# BitDogLab_V7.net
KiCad netlist of a schematic drawn in Altium Designer
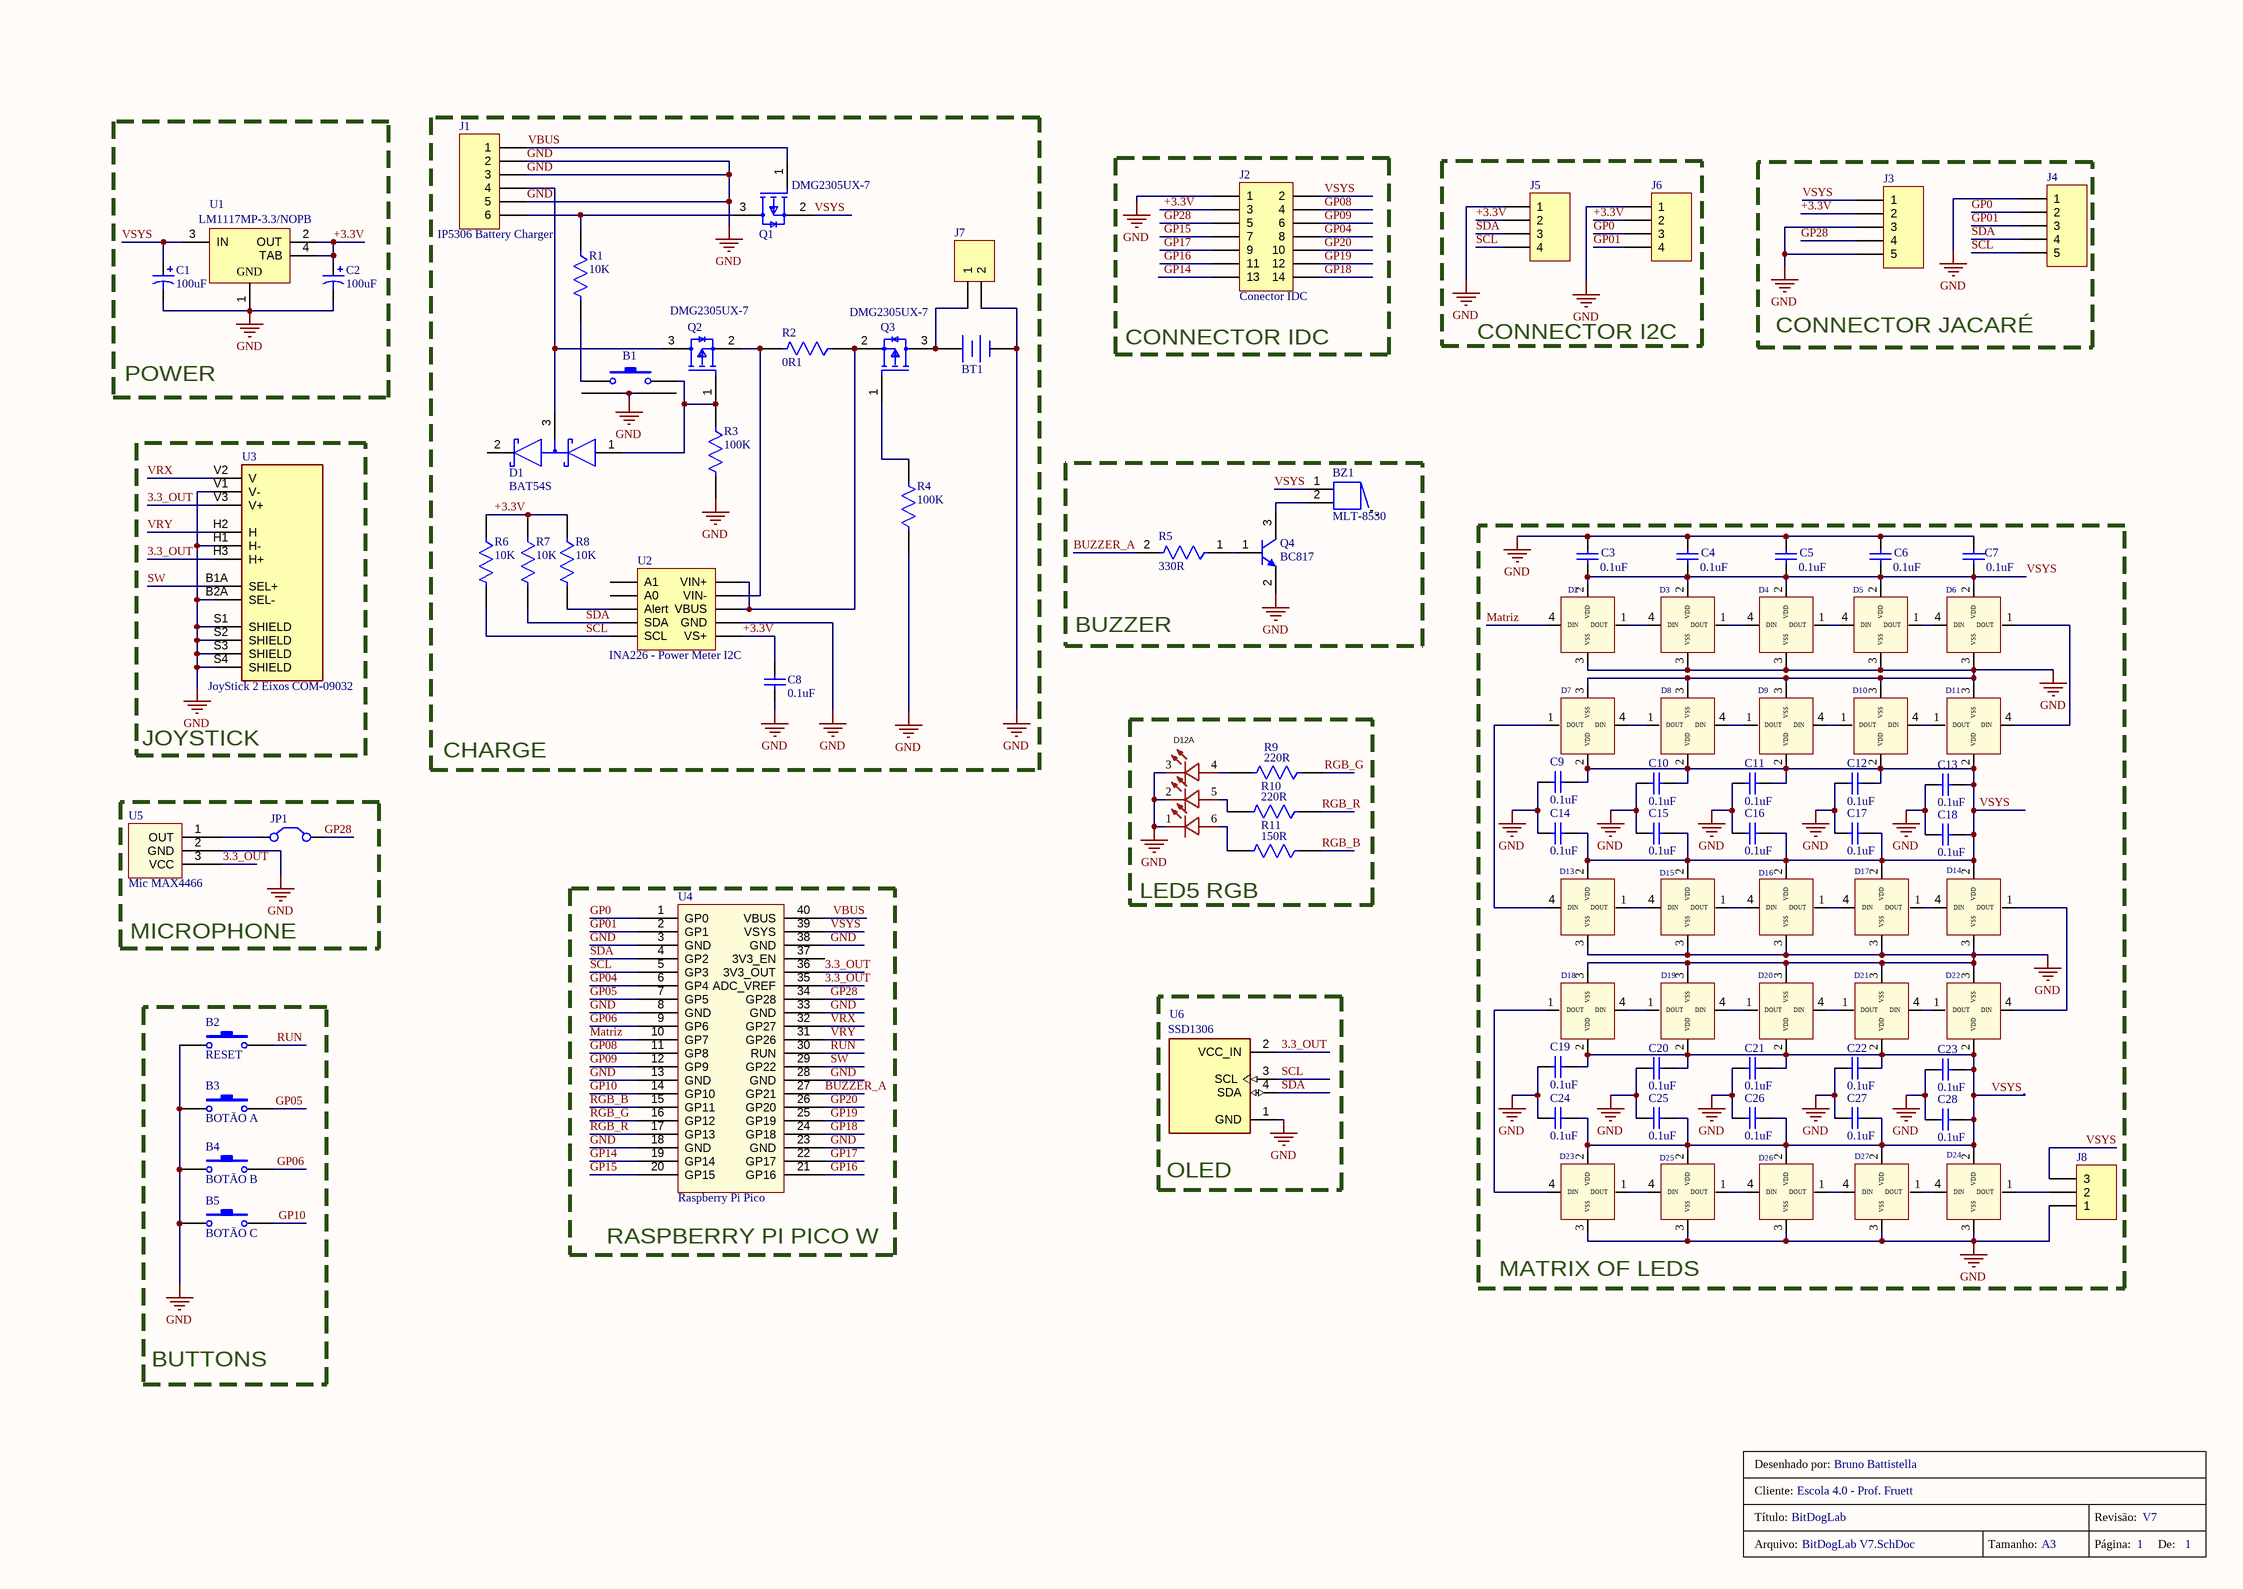
[diagram p0: BitDogLab V7.SchDoc]

(export (version "E")
  (design (tool "Eeschema 10.0.6"))
  (components
    (comp (ref "B1")
      (value "Desliga")
      (footprint "Componentes e Conectores:CHAVE TÁCTIL SMD 90")
      (description "Botão Desliga Placa")
      (libsource (lib "Componentes Bruno") (part "Push Buttom SMD 90 graus"))
    )
    (comp (ref "B2")
      (value "RESET")
      (footprint "Componentes e Conectores:CHAVE TÁCTIL SMD")
      (description "Botão Reset")
      (libsource (lib "Miscellaneous Devices") (part "SW-PB"))
    )
    (comp (ref "B3")
      (value "BOTÃO A")
      (footprint "Componentes e Conectores:CHAVE TÁCTIL 12mm - SMD")
      (description "CHAVE TÁCTIL 12mm - SMD")
      (libsource (lib "Miscellaneous Devices") (part "SW-PB"))
    )
    (comp (ref "B4")
      (value "BOTÃO B")
      (footprint "Componentes e Conectores:CHAVE TÁCTIL 12mm - SMD")
      (description "CHAVE TÁCTIL 12mm - SMD")
      (libsource (lib "Miscellaneous Devices") (part "SW-PB"))
    )
    (comp (ref "B5")
      (value "BOTÃO C")
      (footprint "Componentes e Conectores:CHAVE TÁCTIL 12mm - SMD")
      (description "CHAVE TÁCTIL 12mm - SMD")
      (libsource (lib "Miscellaneous Devices") (part "SW-PB"))
    )
    (comp (ref "BT1")
      (value "FP-1043P-MFG")
      (footprint "Componentes e Conectores:Bateria 18650 - SMD")
      (description "Bateria 18650 3,7V")
      (libsource (lib "Miscellaneous Devices") (part "Battery"))
    )
    (comp (ref "BZ1")
      (value "MLT-8530")
      (footprint "Componentes e Conectores:Buzzer SMD - MLT-8530")
      (description "Buzzer SMD")
      (libsource (lib "Miscellaneous Devices") (part "Buzzer"))
    )
    (comp (ref "C1")
      (value "100uF")
      (footprint "Componentes e Conectores:Capacitor SMD - 6.3 x 5.4mm")
      (description "Capacitor Eletrolítico 100uF  SMD 6.3 x 5.4 mm")
      (fields (field (name "Comment") "Capacitor Eletrolítico SMD,D6.3xL5.4mm"))
      (libsource (lib "Miscellaneous Devices") (part "Cap Pol1"))
    )
    (comp (ref "C2")
      (value "100uF")
      (footprint "Componentes e Conectores:Capacitor SMD - 6.3 x 5.4mm")
      (description "Capacitor Eletrolítico 100uF  SMD 6.3 x 5.4 mm")
      (fields (field (name "Comment") "Capacitor Eletrolítico SMD,D6.3xL5.4mm"))
      (libsource (lib "Miscellaneous Devices") (part "Cap Pol1"))
    )
    (comp (ref "C3")
      (value "0.1uF")
      (footprint "Componentes e Conectores:Capacitor SMD 0402")
      (description "Capacitor SMD 0402")
      (fields (field (name "Comment") "Cap"))
      (libsource (lib "Miscellaneous Devices") (part "Cap"))
    )
    (comp (ref "C4")
      (value "0.1uF")
      (footprint "Componentes e Conectores:Capacitor SMD 0402")
      (description "Capacitor SMD 0402")
      (fields (field (name "Comment") "Cap"))
      (libsource (lib "Miscellaneous Devices") (part "Cap"))
    )
    (comp (ref "C5")
      (value "0.1uF")
      (footprint "Componentes e Conectores:Capacitor SMD 0402")
      (description "Capacitor SMD 0402")
      (fields (field (name "Comment") "Cap"))
      (libsource (lib "Miscellaneous Devices") (part "Cap"))
    )
    (comp (ref "C6")
      (value "0.1uF")
      (footprint "Componentes e Conectores:Capacitor SMD 0402")
      (description "Capacitor SMD 0402")
      (fields (field (name "Comment") "Cap"))
      (libsource (lib "Miscellaneous Devices") (part "Cap"))
    )
    (comp (ref "C7")
      (value "0.1uF")
      (footprint "Componentes e Conectores:Capacitor SMD 0402")
      (description "Capacitor SMD 0402")
      (fields (field (name "Comment") "Cap"))
      (libsource (lib "Miscellaneous Devices") (part "Cap"))
    )
    (comp (ref "C8")
      (value "0.1uF")
      (footprint "Componentes e Conectores:Capacitor SMD 0603")
      (description "Capacitor SMD 0402")
      (fields (field (name "Comment") "Cap"))
      (libsource (lib "Miscellaneous Devices") (part "Cap"))
    )
    (comp (ref "C9")
      (value "0.1uF")
      (footprint "Componentes e Conectores:Capacitor SMD 0402")
      (description "Capacitor SMD 0402")
      (fields (field (name "Comment") "Cap"))
      (libsource (lib "Miscellaneous Devices") (part "Cap"))
    )
    (comp (ref "C10")
      (value "0.1uF")
      (footprint "Componentes e Conectores:Capacitor SMD 0402")
      (description "Capacitor SMD 0402")
      (fields (field (name "Comment") "Cap"))
      (libsource (lib "Miscellaneous Devices") (part "Cap"))
    )
    (comp (ref "C11")
      (value "0.1uF")
      (footprint "Componentes e Conectores:Capacitor SMD 0402")
      (description "Capacitor SMD 0402")
      (fields (field (name "Comment") "Cap"))
      (libsource (lib "Miscellaneous Devices") (part "Cap"))
    )
    (comp (ref "C12")
      (value "0.1uF")
      (footprint "Componentes e Conectores:Capacitor SMD 0402")
      (description "Capacitor SMD 0402")
      (fields (field (name "Comment") "Cap"))
      (libsource (lib "Miscellaneous Devices") (part "Cap"))
    )
    (comp (ref "C13")
      (value "0.1uF")
      (footprint "Componentes e Conectores:Capacitor SMD 0402")
      (description "Capacitor SMD 0402")
      (fields (field (name "Comment") "Cap"))
      (libsource (lib "Miscellaneous Devices") (part "Cap"))
    )
    (comp (ref "C14")
      (value "0.1uF")
      (footprint "Componentes e Conectores:Capacitor SMD 0402")
      (description "Capacitor SMD 0402")
      (fields (field (name "Comment") "Cap"))
      (libsource (lib "Miscellaneous Devices") (part "Cap"))
    )
    (comp (ref "C15")
      (value "0.1uF")
      (footprint "Componentes e Conectores:Capacitor SMD 0402")
      (description "Capacitor SMD 0402")
      (fields (field (name "Comment") "Cap"))
      (libsource (lib "Miscellaneous Devices") (part "Cap"))
    )
    (comp (ref "C16")
      (value "0.1uF")
      (footprint "Componentes e Conectores:Capacitor SMD 0402")
      (description "Capacitor SMD 0402")
      (fields (field (name "Comment") "Cap"))
      (libsource (lib "Miscellaneous Devices") (part "Cap"))
    )
    (comp (ref "C17")
      (value "0.1uF")
      (footprint "Componentes e Conectores:Capacitor SMD 0402")
      (description "Capacitor SMD 0402")
      (fields (field (name "Comment") "Cap"))
      (libsource (lib "Miscellaneous Devices") (part "Cap"))
    )
    (comp (ref "C18")
      (value "0.1uF")
      (footprint "Componentes e Conectores:Capacitor SMD 0402")
      (description "Capacitor SMD 0402")
      (fields (field (name "Comment") "Cap"))
      (libsource (lib "Miscellaneous Devices") (part "Cap"))
    )
    (comp (ref "C19")
      (value "0.1uF")
      (footprint "Componentes e Conectores:Capacitor SMD 0402")
      (description "Capacitor SMD 0402")
      (fields (field (name "Comment") "Cap"))
      (libsource (lib "Miscellaneous Devices") (part "Cap"))
    )
    (comp (ref "C20")
      (value "0.1uF")
      (footprint "Componentes e Conectores:Capacitor SMD 0402")
      (description "Capacitor SMD 0402")
      (fields (field (name "Comment") "Cap"))
      (libsource (lib "Miscellaneous Devices") (part "Cap"))
    )
    (comp (ref "C21")
      (value "0.1uF")
      (footprint "Componentes e Conectores:Capacitor SMD 0402")
      (description "Capacitor SMD 0402")
      (fields (field (name "Comment") "Cap"))
      (libsource (lib "Miscellaneous Devices") (part "Cap"))
    )
    (comp (ref "C22")
      (value "0.1uF")
      (footprint "Componentes e Conectores:Capacitor SMD 0402")
      (description "Capacitor SMD 0402")
      (fields (field (name "Comment") "Cap"))
      (libsource (lib "Miscellaneous Devices") (part "Cap"))
    )
    (comp (ref "C23")
      (value "0.1uF")
      (footprint "Componentes e Conectores:Capacitor SMD 0402")
      (description "Capacitor SMD 0402")
      (fields (field (name "Comment") "Cap"))
      (libsource (lib "Miscellaneous Devices") (part "Cap"))
    )
    (comp (ref "C24")
      (value "0.1uF")
      (footprint "Componentes e Conectores:Capacitor SMD 0402")
      (description "Capacitor SMD 0402")
      (fields (field (name "Comment") "Cap"))
      (libsource (lib "Miscellaneous Devices") (part "Cap"))
    )
    (comp (ref "C25")
      (value "0.1uF")
      (footprint "Componentes e Conectores:Capacitor SMD 0402")
      (description "Capacitor SMD 0402")
      (fields (field (name "Comment") "Cap"))
      (libsource (lib "Miscellaneous Devices") (part "Cap"))
    )
    (comp (ref "C26")
      (value "0.1uF")
      (footprint "Componentes e Conectores:Capacitor SMD 0402")
      (description "Capacitor SMD 0402")
      (fields (field (name "Comment") "Cap"))
      (libsource (lib "Miscellaneous Devices") (part "Cap"))
    )
    (comp (ref "C27")
      (value "0.1uF")
      (footprint "Componentes e Conectores:Capacitor SMD 0402")
      (description "Capacitor SMD 0402")
      (fields (field (name "Comment") "Cap"))
      (libsource (lib "Miscellaneous Devices") (part "Cap"))
    )
    (comp (ref "C28")
      (value "0.1uF")
      (footprint "Componentes e Conectores:Capacitor SMD 0402")
      (description "Capacitor SMD 0402")
      (fields (field (name "Comment") "Cap"))
      (libsource (lib "Miscellaneous Devices") (part "Cap"))
    )
    (comp (ref "D1")
      (value "BAT54S")
      (footprint "FP-6_541-5014_01-4-MFG")
      (description "Diodo Schottky SOT23")
      (fields
        (field (name "MANUFACTURER PART NUMBER") "BAT54S-E3-08")
        (field (name "OCTOPART") "https://octopart.com/bat54s-e3-08-vishay-29186616")
      )
      (libsource (lib "Altium Content Vault") (part "826853e049917e74922d2434823b145"))
    )
    (comp (ref "D2")
      (value "XINGLIGHT XL-1615RGBC-WS2812B")
      (footprint "Componentes e Conectores:LED RGB - XL-1615RGBC-WS2812B")
      (description "LED RGB Endereçável")
      (libsource (lib "Componentes Bruno") (part "LED RGB XL-1615RGBC-WS2812B"))
    )
    (comp (ref "D3")
      (value "XINGLIGHT XL-1615RGBC-WS2812B")
      (footprint "Componentes e Conectores:LED RGB - XL-1615RGBC-WS2812B")
      (description "LED RGB Endereçável")
      (libsource (lib "Componentes Bruno") (part "LED RGB XL-1615RGBC-WS2812B"))
    )
    (comp (ref "D4")
      (value "XINGLIGHT XL-1615RGBC-WS2812B")
      (footprint "Componentes e Conectores:LED RGB - XL-1615RGBC-WS2812B")
      (description "LED RGB Endereçável")
      (libsource (lib "Componentes Bruno") (part "LED RGB XL-1615RGBC-WS2812B"))
    )
    (comp (ref "D5")
      (value "XINGLIGHT XL-1615RGBC-WS2812B")
      (footprint "Componentes e Conectores:LED RGB - XL-1615RGBC-WS2812B")
      (description "LED RGB Endereçável")
      (libsource (lib "Componentes Bruno") (part "LED RGB XL-1615RGBC-WS2812B"))
    )
    (comp (ref "D6")
      (value "XINGLIGHT XL-1615RGBC-WS2812B")
      (footprint "Componentes e Conectores:LED RGB - XL-1615RGBC-WS2812B")
      (description "LED RGB Endereçável")
      (libsource (lib "Componentes Bruno") (part "LED RGB XL-1615RGBC-WS2812B"))
    )
    (comp (ref "D7")
      (value "XINGLIGHT XL-1615RGBC-WS2812B")
      (footprint "Componentes e Conectores:LED RGB - XL-1615RGBC-WS2812B")
      (description "LED RGB Endereçável")
      (libsource (lib "") (part "LED RGB XL-1615RGBC-WS2812B_1"))
    )
    (comp (ref "D8")
      (value "XINGLIGHT XL-1615RGBC-WS2812B")
      (footprint "Componentes e Conectores:LED RGB - XL-1615RGBC-WS2812B")
      (description "LED RGB Endereçável")
      (libsource (lib "") (part "LED RGB XL-1615RGBC-WS2812B_1"))
    )
    (comp (ref "D9")
      (value "XINGLIGHT XL-1615RGBC-WS2812B")
      (footprint "Componentes e Conectores:LED RGB - XL-1615RGBC-WS2812B")
      (description "LED RGB Endereçável")
      (libsource (lib "") (part "LED RGB XL-1615RGBC-WS2812B_1"))
    )
    (comp (ref "D10")
      (value "XINGLIGHT XL-1615RGBC-WS2812B")
      (footprint "Componentes e Conectores:LED RGB - XL-1615RGBC-WS2812B")
      (description "LED RGB Endereçável")
      (libsource (lib "") (part "LED RGB XL-1615RGBC-WS2812B_1"))
    )
    (comp (ref "D11")
      (value "XINGLIGHT XL-1615RGBC-WS2812B")
      (footprint "Componentes e Conectores:LED RGB - XL-1615RGBC-WS2812B")
      (description "LED RGB Endereçável")
      (libsource (lib "") (part "LED RGB XL-1615RGBC-WS2812B_1"))
    )
    (comp (ref "D12")
      (value "HL-AF-5060H271BU46FU79GC-S1-THL")
      (footprint "Componentes e Conectores:LED RGB SMD 5050")
      (description "LED RGB 5050")
      (fields (field (name "MANUFACTURER") "HONGLITRONIC(鸿利光电)"))
      (libsource (lib "Componentes Bruno") (part "LED_RGB_5050 - HL-AF-5060H271BU46FU79GC-S1-THL"))
    )
    (comp (ref "D13")
      (value "XINGLIGHT XL-1615RGBC-WS2812B")
      (footprint "Componentes e Conectores:LED RGB - XL-1615RGBC-WS2812B")
      (description "LED RGB Endereçável")
      (libsource (lib "Componentes Bruno") (part "LED RGB XL-1615RGBC-WS2812B"))
    )
    (comp (ref "D14")
      (value "XINGLIGHT XL-1615RGBC-WS2812B")
      (footprint "Componentes e Conectores:LED RGB - XL-1615RGBC-WS2812B")
      (description "LED RGB Endereçável")
      (libsource (lib "Componentes Bruno") (part "LED RGB XL-1615RGBC-WS2812B"))
    )
    (comp (ref "D15")
      (value "XINGLIGHT XL-1615RGBC-WS2812B")
      (footprint "Componentes e Conectores:LED RGB - XL-1615RGBC-WS2812B")
      (description "LED RGB Endereçável")
      (libsource (lib "Componentes Bruno") (part "LED RGB XL-1615RGBC-WS2812B"))
    )
    (comp (ref "D16")
      (value "XINGLIGHT XL-1615RGBC-WS2812B")
      (footprint "Componentes e Conectores:LED RGB - XL-1615RGBC-WS2812B")
      (description "LED RGB Endereçável")
      (libsource (lib "Componentes Bruno") (part "LED RGB XL-1615RGBC-WS2812B"))
    )
    (comp (ref "D17")
      (value "XINGLIGHT XL-1615RGBC-WS2812B")
      (footprint "Componentes e Conectores:LED RGB - XL-1615RGBC-WS2812B")
      (description "LED RGB Endereçável")
      (libsource (lib "Componentes Bruno") (part "LED RGB XL-1615RGBC-WS2812B"))
    )
    (comp (ref "D18")
      (value "XINGLIGHT XL-1615RGBC-WS2812B")
      (footprint "Componentes e Conectores:LED RGB - XL-1615RGBC-WS2812B")
      (description "LED RGB Endereçável")
      (libsource (lib "") (part "LED RGB XL-1615RGBC-WS2812B_1"))
    )
    (comp (ref "D19")
      (value "XINGLIGHT XL-1615RGBC-WS2812B")
      (footprint "Componentes e Conectores:LED RGB - XL-1615RGBC-WS2812B")
      (description "LED RGB Endereçável")
      (libsource (lib "") (part "LED RGB XL-1615RGBC-WS2812B_1"))
    )
    (comp (ref "D20")
      (value "XINGLIGHT XL-1615RGBC-WS2812B")
      (footprint "Componentes e Conectores:LED RGB - XL-1615RGBC-WS2812B")
      (description "LED RGB Endereçável")
      (libsource (lib "") (part "LED RGB XL-1615RGBC-WS2812B_1"))
    )
    (comp (ref "D21")
      (value "XINGLIGHT XL-1615RGBC-WS2812B")
      (footprint "Componentes e Conectores:LED RGB - XL-1615RGBC-WS2812B")
      (description "LED RGB Endereçável")
      (libsource (lib "") (part "LED RGB XL-1615RGBC-WS2812B_1"))
    )
    (comp (ref "D22")
      (value "XINGLIGHT XL-1615RGBC-WS2812B")
      (footprint "Componentes e Conectores:LED RGB - XL-1615RGBC-WS2812B")
      (description "LED RGB Endereçável")
      (libsource (lib "") (part "LED RGB XL-1615RGBC-WS2812B_1"))
    )
    (comp (ref "D23")
      (value "XINGLIGHT XL-1615RGBC-WS2812B")
      (footprint "Componentes e Conectores:LED RGB - XL-1615RGBC-WS2812B")
      (description "LED RGB Endereçável")
      (libsource (lib "Componentes Bruno") (part "LED RGB XL-1615RGBC-WS2812B"))
    )
    (comp (ref "D24")
      (value "XINGLIGHT XL-1615RGBC-WS2812B")
      (footprint "Componentes e Conectores:LED RGB - XL-1615RGBC-WS2812B")
      (description "LED RGB Endereçável")
      (libsource (lib "Componentes Bruno") (part "LED RGB XL-1615RGBC-WS2812B"))
    )
    (comp (ref "D25")
      (value "XINGLIGHT XL-1615RGBC-WS2812B")
      (footprint "Componentes e Conectores:LED RGB - XL-1615RGBC-WS2812B")
      (description "LED RGB Endereçável")
      (libsource (lib "Componentes Bruno") (part "LED RGB XL-1615RGBC-WS2812B"))
    )
    (comp (ref "D26")
      (value "XINGLIGHT XL-1615RGBC-WS2812B")
      (footprint "Componentes e Conectores:LED RGB - XL-1615RGBC-WS2812B")
      (description "LED RGB Endereçável")
      (libsource (lib "Componentes Bruno") (part "LED RGB XL-1615RGBC-WS2812B"))
    )
    (comp (ref "D27")
      (value "XINGLIGHT XL-1615RGBC-WS2812B")
      (footprint "Componentes e Conectores:LED RGB - XL-1615RGBC-WS2812B")
      (description "LED RGB Endereçável")
      (libsource (lib "Componentes Bruno") (part "LED RGB XL-1615RGBC-WS2812B"))
    )
    (comp (ref "J1")
      (value "IP5306 Battery Charger")
      (footprint "Componentes e Conectores:Charger Module IP5306")
      (description "Múdulo de Carga Bateria")
      (libsource (lib "Miscellaneous Connectors") (part "Header 6"))
    )
    (comp (ref "J2")
      (value "Conector IDC")
      (footprint "Componentes e Conectores:Conector IDC 14 Pinos")
      (description "Conector IDC 14 Pinos SMT")
      (libsource (lib "Miscellaneous Connectors") (part "Header 7X2"))
    )
    (comp (ref "J3")
      (value "Header 5")
      (footprint "HDR1X5")
      (description "Saídas de Expansão")
      (libsource (lib "Miscellaneous Connectors") (part "Header 5"))
    )
    (comp (ref "J4")
      (value "Header 5")
      (footprint "HDR1X5")
      (description "Saídas de Expansão")
      (libsource (lib "Miscellaneous Connectors") (part "Header 5"))
    )
    (comp (ref "J5")
      (value "Header 4")
      (footprint "Componentes e Conectores:Connector XH 1x4")
      (description "Header, 4-Pin")
      (libsource (lib "Miscellaneous Connectors") (part "Header 4"))
    )
    (comp (ref "J6")
      (value "Header 4")
      (footprint "Componentes e Conectores:Connector XH 1x4")
      (description "Header, 4-Pin")
      (libsource (lib "Miscellaneous Connectors") (part "Header 4"))
    )
    (comp (ref "J7")
      (value "KRE")
      (footprint "Componentes e Conectores:HDR1X2 3D Macho")
      (description "Entrada Bateria Externa")
      (libsource (lib "Miscellaneous Connectors") (part "Header 2"))
    )
    (comp (ref "J8")
      (value "Header 3")
      (footprint "Componentes e Conectores:HDR1x3 3D Macho")
      (description "Saída LED Endereçáveis")
      (libsource (lib "Miscellaneous Connectors") (part "Header 3"))
    )
    (comp (ref "JP1")
      (value "Jumper")
      (footprint "Componentes e Conectores:HDR1x3 3D Macho")
      (description "Liga Microfone")
      (libsource (lib "Miscellaneous Devices") (part "Jumper"))
    )
    (comp (ref "Q1")
      (value "DMG2305UX-7")
      (footprint "FP-SOT23-IPC_B")
      (description "MOSFET P-CH 20V 4.2A SOT23")
      (libsource (lib "Altium Content Vault") (part "87831b450059b469d4a68f5364f4496"))
    )
    (comp (ref "Q2")
      (value "DMG2305UX-7")
      (footprint "FP-SOT23-IPC_B")
      (description "MOSFET P-CH 20V 4.2A SOT23")
      (libsource (lib "Altium Content Vault") (part "87831b450059b469d4a68f5364f4496"))
    )
    (comp (ref "Q3")
      (value "DMG2305UX-7")
      (footprint "FP-SOT23-IPC_B")
      (description "MOSFET P-CH 20V 4.2A SOT23")
      (libsource (lib "Altium Content Vault") (part "87831b450059b469d4a68f5364f4496"))
    )
    (comp (ref "Q4")
      (value "BC817")
      (footprint "ONSC-SOT-23-3-318-08_V")
      (description "General Purpose Transistor, NPN Silicon, 3-Pin SOT-23, Pb-Free, Tape and Reel")
      (fields (field (name "PARTNUMBER") "BC817-16LT1G") (field (name "MANUFACTURER") "On Semiconductor"))
      (libsource (lib "Altium Content Vault") (part "ONSC-NPN-B1E2C3-3"))
    )
    (comp (ref "R1")
      (value "10K")
      (footprint "FP-CRCW0603-e3-IPC_C")
      (description "RES Thick Film, 10kΩ, 1%, 0.1W, 100ppm/°C, 0603")
      (fields (field (name "TOLERANCE") "1%"))
      (libsource (lib "Altium Content Vault") (part "1029c3af85768c4190bb7ad29bc67b5"))
    )
    (comp (ref "R2")
      (value "0R1")
      (footprint "FP-RL2512-MFG")
      (description "RES 0.1 OHM 1% 1W 2512")
      (fields
        (field (name "OCTOPART") "https://octopart.com/rl2512fk-070r1l-yageo-42334369")
        (field (name "MANUFACTURER") "YAGEO")
      )
      (libsource (lib "Altium Content Vault") (part "1029c3af85768c4190bb7ad29bc67b5"))
    )
    (comp (ref "R3")
      (value "100K")
      (footprint "FP-CRCW0603-e3-IPC_C")
      (description "RES Thick Film, 100kΩ, 1%, 0.1W, 100ppm/°C, 0603")
      (fields (field (name "TOLERANCE") "1%"))
      (libsource (lib "Altium Content Vault") (part "1029c3af85768c4190bb7ad29bc67b5"))
    )
    (comp (ref "R4")
      (value "100K")
      (footprint "FP-CRCW0603-e3-IPC_C")
      (description "RES Thick Film, 100kΩ, 1%, 0.1W, 100ppm/°C, 0603")
      (fields (field (name "TOLERANCE") "1%"))
      (libsource (lib "Altium Content Vault") (part "1029c3af85768c4190bb7ad29bc67b5"))
    )
    (comp (ref "R5")
      (value "330R")
      (footprint "FP-CRCW0603-e3-IPC_C")
      (description "RES Thick Film, 330Ω, 1%, 0.1W, 100ppm/°C, 0603")
      (fields (field (name "TOLERANCE") "1%"))
      (libsource (lib "") (part "1029c3af85768c4190bb7ad29bc67b5_1"))
    )
    (comp (ref "R6")
      (value "10K")
      (footprint "FP-CRCW0603-e3-IPC_C")
      (description "RES Thick Film, 10kΩ, 1%, 0.1W, 100ppm/°C, 0603")
      (fields (field (name "TOLERANCE") "1%"))
      (libsource (lib "Altium Content Vault") (part "1029c3af85768c4190bb7ad29bc67b5"))
    )
    (comp (ref "R7")
      (value "10K")
      (footprint "FP-CRCW0603-e3-IPC_C")
      (description "RES Thick Film, 10kΩ, 1%, 0.1W, 100ppm/°C, 0603")
      (fields (field (name "TOLERANCE") "1%"))
      (libsource (lib "Altium Content Vault") (part "1029c3af85768c4190bb7ad29bc67b5"))
    )
    (comp (ref "R8")
      (value "10K")
      (footprint "FP-CRCW0603-e3-IPC_C")
      (description "RES Thick Film, 10kΩ, 1%, 0.1W, 100ppm/°C, 0603")
      (fields (field (name "TOLERANCE") "1%"))
      (libsource (lib "Altium Content Vault") (part "1029c3af85768c4190bb7ad29bc67b5"))
    )
    (comp (ref "R9")
      (value "220R")
      (footprint "FP-CRCW0603-e3-IPC_C")
      (description "RES Thick Film, 220Ω, 1%, 0.1W, 100ppm/°C, 0603")
      (fields (field (name "TOLERANCE") "1%"))
      (libsource (lib "Altium Content Vault") (part "1029c3af85768c4190bb7ad29bc67b5"))
    )
    (comp (ref "R10")
      (value "220R")
      (footprint "FP-CRCW0603-e3-IPC_C")
      (description "RES Thick Film, 220Ω, 1%, 0.1W, 100ppm/°C, 0603")
      (fields (field (name "TOLERANCE") "1%"))
      (libsource (lib "Altium Content Vault") (part "1029c3af85768c4190bb7ad29bc67b5"))
    )
    (comp (ref "R11")
      (value "150R")
      (footprint "FP-CRCW0603-e3-IPC_C")
      (description "RES Thick Film, 150Ω, 1%, 0.1W, 100ppm/°C, 0603")
      (fields (field (name "TOLERANCE") "1%"))
      (libsource (lib "Altium Content Vault") (part "1029c3af85768c4190bb7ad29bc67b5"))
    )
    (comp (ref "U1")
      (value "LM1117MP-3.3/NOPB")
      (footprint "DCY0004A_L")
      (description "800mA Low-Dropout Linear Regulator, 4-pin SOT-223, Pb-Free")
      (fields (field (name "MANUFACTURER") "Texas Instruments"))
      (libsource (lib "Altium Content Vault") (part "PM-REG-LM1086-SOT4"))
    )
    (comp (ref "U2")
      (value "INA226 - Power Meter I2C")
      (footprint "Componentes e Conectores:MSOP 10 Pinos")
      (description "Ultra-Precise I2C Output Current, Voltage, and Power Monitor")
      (libsource (lib "Componentes Bruno") (part "INA226"))
    )
    (comp (ref "U3")
      (value "JoyStick 2 Eixos COM-09032")
      (footprint "Componentes e Conectores:JoyStick PCB - PS5 3.0")
      (description "Joystick Analógico (Resistivo e de Efeito Hall)")
      (libsource (lib "Componentes Bruno") (part "JoyStick COM-09032"))
    )
    (comp (ref "U4")
      (value "Raspberry Pi Pico")
      (footprint "Componentes e Conectores:Raspberry Pi Pico W - Header SMD Tipo 1 e 2")
      (description "RP2040 Raspberry Pi Pico - ARMÂ® CortexÂ®-M0+ MCU 32-Bit Embedded Evaluation Board")
      (fields (field (name "MF") "Raspberry Pi") (field (name "MP") "SC0918"))
      (libsource (lib "Componentes Bruno") (part "Raspberry Pi Pico W"))
    )
    (comp (ref "U5")
      (value "Mic MAX4466")
      (footprint "Componentes e Conectores:MAX4466")
      (description "Módulo de Microfone")
      (libsource (lib "Componentes Bruno") (part "MAX4466 - Módulo Microfone"))
    )
    (comp (ref "U6")
      (value "SSD1306")
      (footprint "Componentes e Conectores:DISPLAY OLED 128x128 e 128x64")
      (description "0.96\" 128 X 64 MONOCHROME GRAPHIC OLED DISPLAY MODULE - I2C")
      (fields (field (name "MF") "Display Module") (field (name "MP") "DM-OLED096-636"))
      (libsource (lib "Componentes Bruno") (part "SSD1306 - DISPLAY OLED"))
    )
  )
  (nets
    (net (code "1") (name "/+3.3V") (class "Default")
      (node (ref "C2") (pin "1") (pinfunction "1_1") (pintype "passive"))
      (node (ref "C8") (pin "1") (pinfunction "1_1") (pintype "passive"))
      (node (ref "J2") (pin "3") (pinfunction "3_3") (pintype "passive"))
      (node (ref "J3") (pin "2") (pinfunction "2_2") (pintype "passive"))
      (node (ref "J5") (pin "2") (pinfunction "2_2") (pintype "passive"))
      (node (ref "J6") (pin "2") (pinfunction "2_2") (pintype "passive"))
      (node (ref "R6") (pin "1") (pinfunction "1_1") (pintype "passive"))
      (node (ref "R7") (pin "1") (pinfunction "1_1") (pintype "passive"))
      (node (ref "R8") (pin "1") (pinfunction "1_1") (pintype "passive"))
      (node (ref "U1") (pin "2") (pinfunction "OUT_2") (pintype "power_in"))
      (node (ref "U1") (pin "4") (pinfunction "TAB_4") (pintype "power_in"))
      (node (ref "U2") (pin "6") (pinfunction "VS+_6") (pintype "passive"))
    )
    (net (code "2") (name "/3.3_OUT") (class "Default")
      (node (ref "U3") (pin "H3") (pinfunction "H+_H3") (pintype "passive"))
      (node (ref "U3") (pin "V3") (pinfunction "V+_V3") (pintype "passive"))
      (node (ref "U4") (pin "35") (pinfunction "ADC_VREF_35") (pintype "passive"))
      (node (ref "U4") (pin "36") (pinfunction "3V3_OUT_36") (pintype "passive"))
      (node (ref "U5") (pin "3") (pinfunction "VCC_3") (pintype "passive"))
      (node (ref "U6") (pin "2") (pinfunction "VCC_IN_2") (pintype "power_in"))
    )
    (net (code "3") (name "/BUZZER_A") (class "Default")
      (node (ref "R5") (pin "2") (pinfunction "2_2") (pintype "passive"))
      (node (ref "U4") (pin "27") (pinfunction "GP21_27") (pintype "passive"))
    )
    (net (code "4") (name "/GP0") (class "Default")
      (node (ref "J4") (pin "2") (pinfunction "2_2") (pintype "passive"))
      (node (ref "J6") (pin "3") (pinfunction "3_3") (pintype "passive"))
      (node (ref "U4") (pin "1") (pinfunction "GP0_1") (pintype "passive"))
    )
    (net (code "5") (name "/GP01") (class "Default")
      (node (ref "J4") (pin "3") (pinfunction "3_3") (pintype "passive"))
      (node (ref "J6") (pin "4") (pinfunction "4_4") (pintype "passive"))
      (node (ref "U4") (pin "2") (pinfunction "GP1_2") (pintype "passive"))
    )
    (net (code "6") (name "/GP04") (class "Default")
      (node (ref "J2") (pin "8") (pinfunction "8_8") (pintype "passive"))
      (node (ref "U4") (pin "6") (pinfunction "GP4_6") (pintype "passive"))
    )
    (net (code "7") (name "/GP05") (class "Default")
      (node (ref "B3") (pin "2") (pinfunction "2_2") (pintype "passive"))
      (node (ref "U4") (pin "7") (pinfunction "GP5_7") (pintype "passive"))
    )
    (net (code "8") (name "/GP06") (class "Default")
      (node (ref "B4") (pin "2") (pinfunction "2_2") (pintype "passive"))
      (node (ref "U4") (pin "9") (pinfunction "GP6_9") (pintype "passive"))
    )
    (net (code "9") (name "/GP08") (class "Default")
      (node (ref "J2") (pin "4") (pinfunction "4_4") (pintype "passive"))
      (node (ref "U4") (pin "11") (pinfunction "GP8_11") (pintype "passive"))
    )
    (net (code "10") (name "/GP09") (class "Default")
      (node (ref "J2") (pin "6") (pinfunction "6_6") (pintype "passive"))
      (node (ref "U4") (pin "12") (pinfunction "GP9_12") (pintype "passive"))
    )
    (net (code "11") (name "/GP10") (class "Default")
      (node (ref "B5") (pin "2") (pinfunction "2_2") (pintype "passive"))
      (node (ref "U4") (pin "14") (pinfunction "GP10_14") (pintype "passive"))
    )
    (net (code "12") (name "/GP14") (class "Default")
      (node (ref "J2") (pin "13") (pinfunction "13_13") (pintype "passive"))
      (node (ref "U4") (pin "19") (pinfunction "GP14_19") (pintype "passive"))
    )
    (net (code "13") (name "/GP15") (class "Default")
      (node (ref "J2") (pin "7") (pinfunction "7_7") (pintype "passive"))
      (node (ref "U4") (pin "20") (pinfunction "GP15_20") (pintype "passive"))
    )
    (net (code "14") (name "/GP16") (class "Default")
      (node (ref "J2") (pin "11") (pinfunction "11_11") (pintype "passive"))
      (node (ref "U4") (pin "21") (pinfunction "GP16_21") (pintype "passive"))
    )
    (net (code "15") (name "/GP17") (class "Default")
      (node (ref "J2") (pin "9") (pinfunction "9_9") (pintype "passive"))
      (node (ref "U4") (pin "22") (pinfunction "GP17_22") (pintype "passive"))
    )
    (net (code "16") (name "/GP18") (class "Default")
      (node (ref "J2") (pin "14") (pinfunction "14_14") (pintype "passive"))
      (node (ref "U4") (pin "24") (pinfunction "GP18_24") (pintype "passive"))
    )
    (net (code "17") (name "/GP19") (class "Default")
      (node (ref "J2") (pin "12") (pinfunction "12_12") (pintype "passive"))
      (node (ref "U4") (pin "25") (pinfunction "GP19_25") (pintype "passive"))
    )
    (net (code "18") (name "/GP20") (class "Default")
      (node (ref "J2") (pin "10") (pinfunction "10_10") (pintype "passive"))
      (node (ref "U4") (pin "26") (pinfunction "GP20_26") (pintype "passive"))
    )
    (net (code "19") (name "/GP28") (class "Default")
      (node (ref "J2") (pin "5") (pinfunction "5_5") (pintype "passive"))
      (node (ref "J3") (pin "4") (pinfunction "4_4") (pintype "passive"))
      (node (ref "JP1") (pin "2") (pinfunction "C2_2") (pintype "passive"))
      (node (ref "U4") (pin "34") (pinfunction "GP28_34") (pintype "passive"))
    )
    (net (code "20") (name "/Matriz") (class "Default")
      (node (ref "D2") (pin "4") (pinfunction "DIN_4") (pintype "passive"))
      (node (ref "U4") (pin "10") (pinfunction "GP7_10") (pintype "passive"))
    )
    (net (code "21") (name "/RGB_B") (class "Default")
      (node (ref "R11") (pin "1") (pinfunction "1_1") (pintype "passive"))
      (node (ref "U4") (pin "15") (pinfunction "GP11_15") (pintype "passive"))
    )
    (net (code "22") (name "/RGB_G") (class "Default")
      (node (ref "R9") (pin "1") (pinfunction "1_1") (pintype "passive"))
      (node (ref "U4") (pin "16") (pinfunction "GP12_16") (pintype "passive"))
    )
    (net (code "23") (name "/RGB_R") (class "Default")
      (node (ref "R10") (pin "1") (pinfunction "1_1") (pintype "passive"))
      (node (ref "U4") (pin "17") (pinfunction "GP13_17") (pintype "passive"))
    )
    (net (code "24") (name "/RUN") (class "Default")
      (node (ref "B2") (pin "2") (pinfunction "2_2") (pintype "passive"))
      (node (ref "U4") (pin "30") (pinfunction "RUN_30") (pintype "passive"))
    )
    (net (code "25") (name "/SCL") (class "Default")
      (node (ref "J4") (pin "5") (pinfunction "5_5") (pintype "passive"))
      (node (ref "J5") (pin "4") (pinfunction "4_4") (pintype "passive"))
      (node (ref "R6") (pin "2") (pinfunction "2_2") (pintype "passive"))
      (node (ref "U2") (pin "5") (pinfunction "SCL_5") (pintype "passive"))
      (node (ref "U4") (pin "5") (pinfunction "GP3_5") (pintype "passive"))
      (node (ref "U6") (pin "3") (pinfunction "SCL_3") (pintype "input"))
    )
    (net (code "26") (name "/SDA") (class "Default")
      (node (ref "J4") (pin "4") (pinfunction "4_4") (pintype "passive"))
      (node (ref "J5") (pin "3") (pinfunction "3_3") (pintype "passive"))
      (node (ref "R7") (pin "2") (pinfunction "2_2") (pintype "passive"))
      (node (ref "U2") (pin "4") (pinfunction "SDA_4") (pintype "passive"))
      (node (ref "U4") (pin "4") (pinfunction "GP2_4") (pintype "passive"))
      (node (ref "U6") (pin "4") (pinfunction "SDA_4") (pintype "bidirectional"))
    )
    (net (code "27") (name "/SW") (class "Default")
      (node (ref "U3") (pin "B1A") (pinfunction "SEL+_B1A") (pintype "passive"))
      (node (ref "U4") (pin "29") (pinfunction "GP22_29") (pintype "passive"))
    )
    (net (code "28") (name "/VBUS") (class "Default")
      (node (ref "J1") (pin "1") (pinfunction "1_1") (pintype "passive"))
      (node (ref "Q1") (pin "1") (pinfunction "GATE_1") (pintype "passive"))
      (node (ref "U4") (pin "40") (pinfunction "VBUS_40") (pintype "passive"))
    )
    (net (code "29") (name "/VRX") (class "Default")
      (node (ref "U3") (pin "V2") (pinfunction "V_V2") (pintype "passive"))
      (node (ref "U4") (pin "32") (pinfunction "GP27_32") (pintype "passive"))
    )
    (net (code "30") (name "/VRY") (class "Default")
      (node (ref "U3") (pin "H2") (pinfunction "H_H2") (pintype "passive"))
      (node (ref "U4") (pin "31") (pinfunction "GP26_31") (pintype "passive"))
    )
    (net (code "31") (name "/VSYS") (class "Default")
      (node (ref "BZ1") (pin "1") (pinfunction "1_1") (pintype "passive"))
      (node (ref "C1") (pin "1") (pinfunction "1_1") (pintype "passive"))
      (node (ref "C10") (pin "1") (pinfunction "1_1") (pintype "passive"))
      (node (ref "C11") (pin "1") (pinfunction "1_1") (pintype "passive"))
      (node (ref "C12") (pin "1") (pinfunction "1_1") (pintype "passive"))
      (node (ref "C13") (pin "1") (pinfunction "1_1") (pintype "passive"))
      (node (ref "C14") (pin "1") (pinfunction "1_1") (pintype "passive"))
      (node (ref "C15") (pin "1") (pinfunction "1_1") (pintype "passive"))
      (node (ref "C16") (pin "1") (pinfunction "1_1") (pintype "passive"))
      (node (ref "C17") (pin "1") (pinfunction "1_1") (pintype "passive"))
      (node (ref "C18") (pin "1") (pinfunction "1_1") (pintype "passive"))
      (node (ref "C19") (pin "1") (pinfunction "1_1") (pintype "passive"))
      (node (ref "C20") (pin "1") (pinfunction "1_1") (pintype "passive"))
      (node (ref "C21") (pin "1") (pinfunction "1_1") (pintype "passive"))
      (node (ref "C22") (pin "1") (pinfunction "1_1") (pintype "passive"))
      (node (ref "C23") (pin "1") (pinfunction "1_1") (pintype "passive"))
      (node (ref "C24") (pin "1") (pinfunction "1_1") (pintype "passive"))
      (node (ref "C25") (pin "1") (pinfunction "1_1") (pintype "passive"))
      (node (ref "C26") (pin "1") (pinfunction "1_1") (pintype "passive"))
      (node (ref "C27") (pin "1") (pinfunction "1_1") (pintype "passive"))
      (node (ref "C28") (pin "1") (pinfunction "1_1") (pintype "passive"))
      (node (ref "C3") (pin "1") (pinfunction "1_1") (pintype "passive"))
      (node (ref "C4") (pin "1") (pinfunction "1_1") (pintype "passive"))
      (node (ref "C5") (pin "1") (pinfunction "1_1") (pintype "passive"))
      (node (ref "C6") (pin "1") (pinfunction "1_1") (pintype "passive"))
      (node (ref "C7") (pin "1") (pinfunction "1_1") (pintype "passive"))
      (node (ref "C9") (pin "1") (pinfunction "1_1") (pintype "passive"))
      (node (ref "D10") (pin "2") (pinfunction "VDD_2") (pintype "passive"))
      (node (ref "D11") (pin "2") (pinfunction "VDD_2") (pintype "passive"))
      (node (ref "D13") (pin "2") (pinfunction "VDD_2") (pintype "passive"))
      (node (ref "D14") (pin "2") (pinfunction "VDD_2") (pintype "passive"))
      (node (ref "D15") (pin "2") (pinfunction "VDD_2") (pintype "passive"))
      (node (ref "D16") (pin "2") (pinfunction "VDD_2") (pintype "passive"))
      (node (ref "D17") (pin "2") (pinfunction "VDD_2") (pintype "passive"))
      (node (ref "D18") (pin "2") (pinfunction "VDD_2") (pintype "passive"))
      (node (ref "D19") (pin "2") (pinfunction "VDD_2") (pintype "passive"))
      (node (ref "D2") (pin "2") (pinfunction "VDD_2") (pintype "passive"))
      (node (ref "D20") (pin "2") (pinfunction "VDD_2") (pintype "passive"))
      (node (ref "D21") (pin "2") (pinfunction "VDD_2") (pintype "passive"))
      (node (ref "D22") (pin "2") (pinfunction "VDD_2") (pintype "passive"))
      (node (ref "D23") (pin "2") (pinfunction "VDD_2") (pintype "passive"))
      (node (ref "D24") (pin "2") (pinfunction "VDD_2") (pintype "passive"))
      (node (ref "D25") (pin "2") (pinfunction "VDD_2") (pintype "passive"))
      (node (ref "D26") (pin "2") (pinfunction "VDD_2") (pintype "passive"))
      (node (ref "D27") (pin "2") (pinfunction "VDD_2") (pintype "passive"))
      (node (ref "D3") (pin "2") (pinfunction "VDD_2") (pintype "passive"))
      (node (ref "D4") (pin "2") (pinfunction "VDD_2") (pintype "passive"))
      (node (ref "D5") (pin "2") (pinfunction "VDD_2") (pintype "passive"))
      (node (ref "D6") (pin "2") (pinfunction "VDD_2") (pintype "passive"))
      (node (ref "D7") (pin "2") (pinfunction "VDD_2") (pintype "passive"))
      (node (ref "D8") (pin "2") (pinfunction "VDD_2") (pintype "passive"))
      (node (ref "D9") (pin "2") (pinfunction "VDD_2") (pintype "passive"))
      (node (ref "J2") (pin "2") (pinfunction "2_2") (pintype "passive"))
      (node (ref "J3") (pin "1") (pinfunction "1_1") (pintype "passive"))
      (node (ref "J8") (pin "3") (pinfunction "3_3") (pintype "passive"))
      (node (ref "Q1") (pin "2") (pinfunction "SOURCE_2") (pintype "passive"))
      (node (ref "U1") (pin "3") (pinfunction "IN_3") (pintype "power_in"))
      (node (ref "U4") (pin "39") (pinfunction "VSYS_39") (pintype "passive"))
    )
    (net (code "32") (name "GND") (class "Default")
      (node (ref "B1") (pin "3") (pinfunction "3_3") (pintype "passive"))
      (node (ref "B1") (pin "4") (pinfunction "4_4") (pintype "passive"))
      (node (ref "B2") (pin "1") (pinfunction "1_1") (pintype "passive"))
      (node (ref "B3") (pin "1") (pinfunction "1_1") (pintype "passive"))
      (node (ref "B4") (pin "1") (pinfunction "1_1") (pintype "passive"))
      (node (ref "B5") (pin "1") (pinfunction "1_1") (pintype "passive"))
      (node (ref "BT1") (pin "1") (pinfunction "-_1") (pintype "passive"))
      (node (ref "C1") (pin "2") (pinfunction "2_2") (pintype "passive"))
      (node (ref "C10") (pin "2") (pinfunction "2_2") (pintype "passive"))
      (node (ref "C11") (pin "2") (pinfunction "2_2") (pintype "passive"))
      (node (ref "C12") (pin "2") (pinfunction "2_2") (pintype "passive"))
      (node (ref "C13") (pin "2") (pinfunction "2_2") (pintype "passive"))
      (node (ref "C14") (pin "2") (pinfunction "2_2") (pintype "passive"))
      (node (ref "C15") (pin "2") (pinfunction "2_2") (pintype "passive"))
      (node (ref "C16") (pin "2") (pinfunction "2_2") (pintype "passive"))
      (node (ref "C17") (pin "2") (pinfunction "2_2") (pintype "passive"))
      (node (ref "C18") (pin "2") (pinfunction "2_2") (pintype "passive"))
      (node (ref "C19") (pin "2") (pinfunction "2_2") (pintype "passive"))
      (node (ref "C2") (pin "2") (pinfunction "2_2") (pintype "passive"))
      (node (ref "C20") (pin "2") (pinfunction "2_2") (pintype "passive"))
      (node (ref "C21") (pin "2") (pinfunction "2_2") (pintype "passive"))
      (node (ref "C22") (pin "2") (pinfunction "2_2") (pintype "passive"))
      (node (ref "C23") (pin "2") (pinfunction "2_2") (pintype "passive"))
      (node (ref "C24") (pin "2") (pinfunction "2_2") (pintype "passive"))
      (node (ref "C25") (pin "2") (pinfunction "2_2") (pintype "passive"))
      (node (ref "C26") (pin "2") (pinfunction "2_2") (pintype "passive"))
      (node (ref "C27") (pin "2") (pinfunction "2_2") (pintype "passive"))
      (node (ref "C28") (pin "2") (pinfunction "2_2") (pintype "passive"))
      (node (ref "C3") (pin "2") (pinfunction "2_2") (pintype "passive"))
      (node (ref "C4") (pin "2") (pinfunction "2_2") (pintype "passive"))
      (node (ref "C5") (pin "2") (pinfunction "2_2") (pintype "passive"))
      (node (ref "C6") (pin "2") (pinfunction "2_2") (pintype "passive"))
      (node (ref "C7") (pin "2") (pinfunction "2_2") (pintype "passive"))
      (node (ref "C8") (pin "2") (pinfunction "2_2") (pintype "passive"))
      (node (ref "C9") (pin "2") (pinfunction "2_2") (pintype "passive"))
      (node (ref "D10") (pin "3") (pinfunction "VSS_3") (pintype "passive"))
      (node (ref "D11") (pin "3") (pinfunction "VSS_3") (pintype "passive"))
      (node (ref "D12") (pin "1") (pintype "passive"))
      (node (ref "D12") (pin "2") (pintype "passive"))
      (node (ref "D12") (pin "3") (pintype "passive"))
      (node (ref "D13") (pin "3") (pinfunction "VSS_3") (pintype "passive"))
      (node (ref "D14") (pin "3") (pinfunction "VSS_3") (pintype "passive"))
      (node (ref "D15") (pin "3") (pinfunction "VSS_3") (pintype "passive"))
      (node (ref "D16") (pin "3") (pinfunction "VSS_3") (pintype "passive"))
      (node (ref "D17") (pin "3") (pinfunction "VSS_3") (pintype "passive"))
      (node (ref "D18") (pin "3") (pinfunction "VSS_3") (pintype "passive"))
      (node (ref "D19") (pin "3") (pinfunction "VSS_3") (pintype "passive"))
      (node (ref "D2") (pin "3") (pinfunction "VSS_3") (pintype "passive"))
      (node (ref "D20") (pin "3") (pinfunction "VSS_3") (pintype "passive"))
      (node (ref "D21") (pin "3") (pinfunction "VSS_3") (pintype "passive"))
      (node (ref "D22") (pin "3") (pinfunction "VSS_3") (pintype "passive"))
      (node (ref "D23") (pin "3") (pinfunction "VSS_3") (pintype "passive"))
      (node (ref "D24") (pin "3") (pinfunction "VSS_3") (pintype "passive"))
      (node (ref "D25") (pin "3") (pinfunction "VSS_3") (pintype "passive"))
      (node (ref "D26") (pin "3") (pinfunction "VSS_3") (pintype "passive"))
      (node (ref "D27") (pin "3") (pinfunction "VSS_3") (pintype "passive"))
      (node (ref "D3") (pin "3") (pinfunction "VSS_3") (pintype "passive"))
      (node (ref "D4") (pin "3") (pinfunction "VSS_3") (pintype "passive"))
      (node (ref "D5") (pin "3") (pinfunction "VSS_3") (pintype "passive"))
      (node (ref "D6") (pin "3") (pinfunction "VSS_3") (pintype "passive"))
      (node (ref "D7") (pin "3") (pinfunction "VSS_3") (pintype "passive"))
      (node (ref "D8") (pin "3") (pinfunction "VSS_3") (pintype "passive"))
      (node (ref "D9") (pin "3") (pinfunction "VSS_3") (pintype "passive"))
      (node (ref "J1") (pin "2") (pinfunction "2_2") (pintype "passive"))
      (node (ref "J1") (pin "3") (pinfunction "3_3") (pintype "passive"))
      (node (ref "J1") (pin "5") (pinfunction "5_5") (pintype "passive"))
      (node (ref "J2") (pin "1") (pinfunction "1_1") (pintype "passive"))
      (node (ref "J3") (pin "3") (pinfunction "3_3") (pintype "passive"))
      (node (ref "J3") (pin "5") (pinfunction "5_5") (pintype "passive"))
      (node (ref "J4") (pin "1") (pinfunction "1_1") (pintype "passive"))
      (node (ref "J5") (pin "1") (pinfunction "1_1") (pintype "passive"))
      (node (ref "J6") (pin "1") (pinfunction "1_1") (pintype "passive"))
      (node (ref "J7") (pin "2") (pinfunction "2_2") (pintype "passive"))
      (node (ref "J8") (pin "1") (pinfunction "1_1") (pintype "passive"))
      (node (ref "Q4") (pin "2") (pinfunction "E_2") (pintype "passive"))
      (node (ref "R3") (pin "2") (pinfunction "2_2") (pintype "passive"))
      (node (ref "R4") (pin "1") (pinfunction "1_1") (pintype "passive"))
      (node (ref "U1") (pin "1") (pinfunction "GND_1") (pintype "power_in"))
      (node (ref "U2") (pin "7") (pinfunction "GND_7") (pintype "passive"))
      (node (ref "U3") (pin "B2A") (pinfunction "SEL-_B2A") (pintype "passive"))
      (node (ref "U3") (pin "H1") (pinfunction "H-_H1") (pintype "passive"))
      (node (ref "U3") (pin "S1") (pinfunction "SHIELD_S1") (pintype "passive"))
      (node (ref "U3") (pin "S2") (pinfunction "SHIELD_S2") (pintype "passive"))
      (node (ref "U3") (pin "S3") (pinfunction "SHIELD_S3") (pintype "passive"))
      (node (ref "U3") (pin "S4") (pinfunction "SHIELD_S4") (pintype "passive"))
      (node (ref "U3") (pin "V1") (pinfunction "V-_V1") (pintype "passive"))
      (node (ref "U4") (pin "13") (pinfunction "GND_13") (pintype "passive"))
      (node (ref "U4") (pin "18") (pinfunction "GND_18") (pintype "passive"))
      (node (ref "U4") (pin "23") (pinfunction "GND_23") (pintype "passive"))
      (node (ref "U4") (pin "28") (pinfunction "GND_28") (pintype "passive"))
      (node (ref "U4") (pin "3") (pinfunction "GND_3") (pintype "passive"))
      (node (ref "U4") (pin "33") (pinfunction "GND_33") (pintype "passive"))
      (node (ref "U4") (pin "38") (pinfunction "GND_38") (pintype "passive"))
      (node (ref "U4") (pin "8") (pinfunction "GND_8") (pintype "passive"))
      (node (ref "U5") (pin "2") (pinfunction "GND_2") (pintype "passive"))
      (node (ref "U6") (pin "1") (pinfunction "GND_1") (pintype "power_in"))
    )
    (net (code "33") (name "Net-(B1-Pad1)") (class "Default")
      (node (ref "B1") (pin "1") (pinfunction "1_1") (pintype "passive"))
      (node (ref "R1") (pin "2") (pinfunction "2_2") (pintype "passive"))
    )
    (net (code "34") (name "Net-(BT1-+)") (class "Default")
      (node (ref "BT1") (pin "2") (pinfunction "+_2") (pintype "passive"))
      (node (ref "J7") (pin "1") (pinfunction "1_1") (pintype "passive"))
      (node (ref "Q3") (pin "3") (pinfunction "DRAIN_3") (pintype "passive"))
    )
    (net (code "35") (name "Net-(D2-DOUT)") (class "Default")
      (node (ref "D2") (pin "1") (pinfunction "DOUT_1") (pintype "passive"))
      (node (ref "D3") (pin "4") (pinfunction "DIN_4") (pintype "passive"))
    )
    (net (code "36") (name "Net-(D3-DOUT)") (class "Default")
      (node (ref "D3") (pin "1") (pinfunction "DOUT_1") (pintype "passive"))
      (node (ref "D4") (pin "4") (pinfunction "DIN_4") (pintype "passive"))
    )
    (net (code "37") (name "Net-(D4-DOUT)") (class "Default")
      (node (ref "D4") (pin "1") (pinfunction "DOUT_1") (pintype "passive"))
      (node (ref "D5") (pin "4") (pinfunction "DIN_4") (pintype "passive"))
    )
    (net (code "38") (name "Net-(D5-DOUT)") (class "Default")
      (node (ref "D5") (pin "1") (pinfunction "DOUT_1") (pintype "passive"))
      (node (ref "D6") (pin "4") (pinfunction "DIN_4") (pintype "passive"))
    )
    (net (code "39") (name "Net-(D7-DIN)") (class "Default")
      (node (ref "D7") (pin "4") (pinfunction "DIN_4") (pintype "passive"))
      (node (ref "D8") (pin "1") (pinfunction "DOUT_1") (pintype "passive"))
    )
    (net (code "40") (name "Net-(D8-DIN)") (class "Default")
      (node (ref "D8") (pin "4") (pinfunction "DIN_4") (pintype "passive"))
      (node (ref "D9") (pin "1") (pinfunction "DOUT_1") (pintype "passive"))
    )
    (net (code "41") (name "Net-(D10-DIN)") (class "Default")
      (node (ref "D10") (pin "4") (pinfunction "DIN_4") (pintype "passive"))
      (node (ref "D11") (pin "1") (pinfunction "DOUT_1") (pintype "passive"))
    )
    (net (code "42") (name "Net-(D10-DOUT)") (class "Default")
      (node (ref "D10") (pin "1") (pinfunction "DOUT_1") (pintype "passive"))
      (node (ref "D9") (pin "4") (pinfunction "DIN_4") (pintype "passive"))
    )
    (net (code "43") (name "Net-(D11-DIN)") (class "Default")
      (node (ref "D11") (pin "4") (pinfunction "DIN_4") (pintype "passive"))
      (node (ref "D6") (pin "1") (pinfunction "DOUT_1") (pintype "passive"))
    )
    (net (code "44") (name "Net-(D12-Pad4)") (class "Default")
      (node (ref "D12") (pin "4") (pintype "passive"))
      (node (ref "R9") (pin "2") (pinfunction "2_2") (pintype "passive"))
    )
    (net (code "45") (name "Net-(D12-Pad5)") (class "Default")
      (node (ref "D12") (pin "5") (pintype "passive"))
      (node (ref "R10") (pin "2") (pinfunction "2_2") (pintype "passive"))
    )
    (net (code "46") (name "Net-(D12-Pad6)") (class "Default")
      (node (ref "D12") (pin "6") (pintype "passive"))
      (node (ref "R11") (pin "2") (pinfunction "2_2") (pintype "passive"))
    )
    (net (code "47") (name "Net-(D13-DIN)") (class "Default")
      (node (ref "D13") (pin "4") (pinfunction "DIN_4") (pintype "passive"))
      (node (ref "D7") (pin "1") (pinfunction "DOUT_1") (pintype "passive"))
    )
    (net (code "48") (name "Net-(D13-DOUT)") (class "Default")
      (node (ref "D13") (pin "1") (pinfunction "DOUT_1") (pintype "passive"))
      (node (ref "D15") (pin "4") (pinfunction "DIN_4") (pintype "passive"))
    )
    (net (code "49") (name "Net-(D14-DIN)") (class "Default")
      (node (ref "D14") (pin "4") (pinfunction "DIN_4") (pintype "passive"))
      (node (ref "D17") (pin "1") (pinfunction "DOUT_1") (pintype "passive"))
    )
    (net (code "50") (name "Net-(D14-DOUT)") (class "Default")
      (node (ref "D14") (pin "1") (pinfunction "DOUT_1") (pintype "passive"))
      (node (ref "D22") (pin "4") (pinfunction "DIN_4") (pintype "passive"))
    )
    (net (code "51") (name "Net-(D15-DOUT)") (class "Default")
      (node (ref "D15") (pin "1") (pinfunction "DOUT_1") (pintype "passive"))
      (node (ref "D16") (pin "4") (pinfunction "DIN_4") (pintype "passive"))
    )
    (net (code "52") (name "Net-(D16-DOUT)") (class "Default")
      (node (ref "D16") (pin "1") (pinfunction "DOUT_1") (pintype "passive"))
      (node (ref "D17") (pin "4") (pinfunction "DIN_4") (pintype "passive"))
    )
    (net (code "53") (name "Net-(D18-DIN)") (class "Default")
      (node (ref "D18") (pin "4") (pinfunction "DIN_4") (pintype "passive"))
      (node (ref "D19") (pin "1") (pinfunction "DOUT_1") (pintype "passive"))
    )
    (net (code "54") (name "Net-(D18-DOUT)") (class "Default")
      (node (ref "D18") (pin "1") (pinfunction "DOUT_1") (pintype "passive"))
      (node (ref "D23") (pin "4") (pinfunction "DIN_4") (pintype "passive"))
    )
    (net (code "55") (name "Net-(D19-DIN)") (class "Default")
      (node (ref "D19") (pin "4") (pinfunction "DIN_4") (pintype "passive"))
      (node (ref "D20") (pin "1") (pinfunction "DOUT_1") (pintype "passive"))
    )
    (net (code "56") (name "Net-(D20-DIN)") (class "Default")
      (node (ref "D20") (pin "4") (pinfunction "DIN_4") (pintype "passive"))
      (node (ref "D21") (pin "1") (pinfunction "DOUT_1") (pintype "passive"))
    )
    (net (code "57") (name "Net-(D21-DIN)") (class "Default")
      (node (ref "D21") (pin "4") (pinfunction "DIN_4") (pintype "passive"))
      (node (ref "D22") (pin "1") (pinfunction "DOUT_1") (pintype "passive"))
    )
    (net (code "58") (name "Net-(D23-DOUT)") (class "Default")
      (node (ref "D23") (pin "1") (pinfunction "DOUT_1") (pintype "passive"))
      (node (ref "D25") (pin "4") (pinfunction "DIN_4") (pintype "passive"))
    )
    (net (code "59") (name "Net-(D24-DIN)") (class "Default")
      (node (ref "D24") (pin "4") (pinfunction "DIN_4") (pintype "passive"))
      (node (ref "D27") (pin "1") (pinfunction "DOUT_1") (pintype "passive"))
    )
    (net (code "60") (name "Net-(D24-DOUT)") (class "Default")
      (node (ref "D24") (pin "1") (pinfunction "DOUT_1") (pintype "passive"))
      (node (ref "J8") (pin "2") (pinfunction "2_2") (pintype "passive"))
    )
    (net (code "61") (name "Net-(D25-DOUT)") (class "Default")
      (node (ref "D25") (pin "1") (pinfunction "DOUT_1") (pintype "passive"))
      (node (ref "D26") (pin "4") (pinfunction "DIN_4") (pintype "passive"))
    )
    (net (code "62") (name "Net-(D26-DOUT)") (class "Default")
      (node (ref "D26") (pin "1") (pinfunction "DOUT_1") (pintype "passive"))
      (node (ref "D27") (pin "4") (pinfunction "DIN_4") (pintype "passive"))
    )
    (net (code "63") (name "Net-(JP1-C1)") (class "Default")
      (node (ref "JP1") (pin "1") (pinfunction "C1_1") (pintype "passive"))
      (node (ref "U5") (pin "1") (pinfunction "OUT_1") (pintype "passive"))
    )
    (net (code "64") (name "Net-(Q1-DRAIN)") (class "Default")
      (node (ref "J1") (pin "6") (pinfunction "6_6") (pintype "passive"))
      (node (ref "Q1") (pin "3") (pinfunction "DRAIN_3") (pintype "passive"))
      (node (ref "R1") (pin "1") (pinfunction "1_1") (pintype "passive"))
    )
    (net (code "65") (name "Net-(Q2-DRAIN)") (class "Default")
      (node (ref "D1") (pin "3") (pinfunction "3_3") (pintype "passive"))
      (node (ref "J1") (pin "4") (pinfunction "4_4") (pintype "passive"))
      (node (ref "Q2") (pin "3") (pinfunction "DRAIN_3") (pintype "passive"))
    )
    (net (code "66") (name "Net-(Q2-GATE)") (class "Default")
      (node (ref "B1") (pin "2") (pinfunction "2_2") (pintype "passive"))
      (node (ref "D1") (pin "1") (pinfunction "1_1") (pintype "passive"))
      (node (ref "Q2") (pin "1") (pinfunction "GATE_1") (pintype "passive"))
      (node (ref "R3") (pin "1") (pinfunction "1_1") (pintype "passive"))
    )
    (net (code "67") (name "Net-(Q2-SOURCE)") (class "Default")
      (node (ref "Q2") (pin "2") (pinfunction "SOURCE_2") (pintype "passive"))
      (node (ref "R2") (pin "2") (pinfunction "2_2") (pintype "passive"))
      (node (ref "U2") (pin "9") (pinfunction "VIN-_9") (pintype "passive"))
    )
    (net (code "68") (name "Net-(Q3-GATE)") (class "Default")
      (node (ref "Q3") (pin "1") (pinfunction "GATE_1") (pintype "passive"))
      (node (ref "R4") (pin "2") (pinfunction "2_2") (pintype "passive"))
    )
    (net (code "69") (name "Net-(Q3-SOURCE)") (class "Default")
      (node (ref "Q3") (pin "2") (pinfunction "SOURCE_2") (pintype "passive"))
      (node (ref "R2") (pin "1") (pinfunction "1_1") (pintype "passive"))
      (node (ref "U2") (pin "10") (pinfunction "VIN+_10") (pintype "passive"))
      (node (ref "U2") (pin "8") (pinfunction "VBUS_8") (pintype "passive"))
    )
    (net (code "70") (name "Net-(Q4-B)") (class "Default")
      (node (ref "Q4") (pin "1") (pinfunction "B_1") (pintype "passive"))
      (node (ref "R5") (pin "1") (pinfunction "1_1") (pintype "passive"))
    )
    (net (code "71") (name "Net-(Q4-C)") (class "Default")
      (node (ref "BZ1") (pin "2") (pinfunction "2_2") (pintype "passive"))
      (node (ref "Q4") (pin "3") (pinfunction "C_3") (pintype "passive"))
    )
    (net (code "72") (name "Net-(U2-Alert)") (class "Default")
      (node (ref "R8") (pin "2") (pinfunction "2_2") (pintype "passive"))
      (node (ref "U2") (pin "3") (pinfunction "Alert_3") (pintype "passive"))
    )
    (net (code "73") (name "unconnected-(BZ1-Pad3)") (class "Default")
      (node (ref "BZ1") (pin "3") (pinfunction "3_3") (pintype "passive"))
    )
    (net (code "74") (name "unconnected-(BZ1-Pad4)") (class "Default")
      (node (ref "BZ1") (pin "4") (pinfunction "4_4") (pintype "passive"))
    )
    (net (code "75") (name "unconnected-(D1-Pad2)") (class "Default")
      (node (ref "D1") (pin "2") (pinfunction "2_2") (pintype "passive"))
    )
    (net (code "76") (name "unconnected-(U2-A0-Pad2)") (class "Default")
      (node (ref "U2") (pin "2") (pinfunction "A0_2") (pintype "passive"))
    )
    (net (code "77") (name "unconnected-(U2-A1-Pad1)") (class "Default")
      (node (ref "U2") (pin "1") (pinfunction "A1_1") (pintype "passive"))
    )
    (net (code "78") (name "unconnected-(U4-3V3_EN-Pad37)") (class "Default")
      (node (ref "U4") (pin "37") (pinfunction "3V3_EN_37") (pintype "passive"))
    )
  )
)
